# reverb.net
KiCad netlist of a schematic drawn in EAGLE
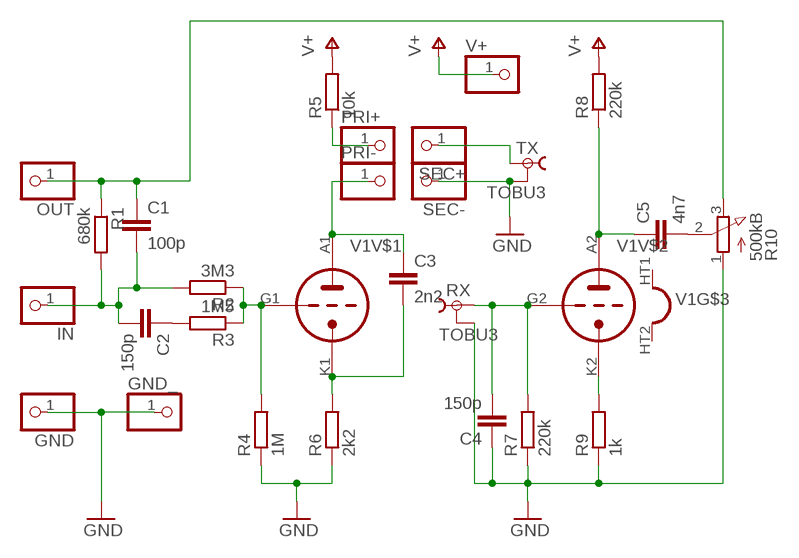
[diagram p0: schematic, sheet 1]

(export (version "E")
  (design (tool "Eeschema 10.0.6"))
  (components
    (comp (ref "C1")
      (value "100p")
      (footprint "eagle-import:C050-030X075")
      (libsource (lib "eagle-import") (part "C-EU050-030X075"))
    )
    (comp (ref "C2")
      (value "150p")
      (footprint "eagle-import:C050-030X075")
      (libsource (lib "eagle-import") (part "C-EU050-030X075"))
    )
    (comp (ref "C3")
      (value "2n2")
      (footprint "eagle-import:C050-030X075")
      (libsource (lib "eagle-import") (part "C-EU050-030X075"))
    )
    (comp (ref "C4")
      (value "150p")
      (footprint "eagle-import:C050-030X075")
      (libsource (lib "eagle-import") (part "C-EU050-030X075"))
    )
    (comp (ref "C5")
      (value "4n7")
      (footprint "eagle-import:C050-045X075")
      (libsource (lib "eagle-import") (part "C-EU050-045X075"))
    )
    (comp (ref "GND")
      (value "PINHD-1X1")
      (footprint "eagle-import:1X01")
      (libsource (lib "eagle-import") (part "PINHD-1X1"))
    )
    (comp (ref "GND_")
      (value "PINHD-1X1")
      (footprint "eagle-import:1X01")
      (libsource (lib "eagle-import") (part "PINHD-1X1"))
    )
    (comp (ref "IN")
      (value "PINHD-1X1")
      (footprint "eagle-import:1X01")
      (libsource (lib "eagle-import") (part "PINHD-1X1"))
    )
    (comp (ref "OUT")
      (value "PINHD-1X1")
      (footprint "eagle-import:1X01")
      (libsource (lib "eagle-import") (part "PINHD-1X1"))
    )
    (comp (ref "PRI+")
      (value "PINHD-1X1")
      (footprint "eagle-import:1X01")
      (libsource (lib "eagle-import") (part "PINHD-1X1"))
    )
    (comp (ref "PRI-")
      (value "PINHD-1X1")
      (footprint "eagle-import:1X01")
      (libsource (lib "eagle-import") (part "PINHD-1X1"))
    )
    (comp (ref "R1")
      (value "680k")
      (footprint "eagle-import:0207_7")
      (libsource (lib "eagle-import") (part "R-EU_0207/7"))
    )
    (comp (ref "R2")
      (value "3M3")
      (footprint "eagle-import:0207_7")
      (libsource (lib "eagle-import") (part "R-EU_0207/7"))
    )
    (comp (ref "R3")
      (value "1M5")
      (footprint "eagle-import:0207_7")
      (libsource (lib "eagle-import") (part "R-EU_0207/7"))
    )
    (comp (ref "R4")
      (value "1M")
      (footprint "eagle-import:0207_7")
      (libsource (lib "eagle-import") (part "R-EU_0207/7"))
    )
    (comp (ref "R5")
      (value "10k")
      (footprint "eagle-import:0207_7")
      (libsource (lib "eagle-import") (part "R-EU_0207/7"))
    )
    (comp (ref "R6")
      (value "2k2")
      (footprint "eagle-import:0207_7")
      (libsource (lib "eagle-import") (part "R-EU_0207/7"))
    )
    (comp (ref "R7")
      (value "220k")
      (footprint "eagle-import:0207_7")
      (libsource (lib "eagle-import") (part "R-EU_0207/7"))
    )
    (comp (ref "R8")
      (value "220k")
      (footprint "eagle-import:0207_7")
      (libsource (lib "eagle-import") (part "R-EU_0207/7"))
    )
    (comp (ref "R9")
      (value "1k")
      (footprint "eagle-import:0207_7")
      (libsource (lib "eagle-import") (part "R-EU_0207/7"))
    )
    (comp (ref "R10")
      (value "500kB")
      (footprint "eagle-import:3RP_1610N")
      (libsource (lib "eagle-import") (part "3RP/1610N"))
    )
    (comp (ref "RX")
      (value "TOBU3")
      (footprint "eagle-import:TOBU3")
      (fields (field (name "MF") "FARNELL") (field (name "MPN") "TOBU 3"))
      (libsource (lib "eagle-import") (part "TOBU3"))
    )
    (comp (ref "SEC+")
      (value "PINHD-1X1")
      (footprint "eagle-import:1X01")
      (libsource (lib "eagle-import") (part "PINHD-1X1"))
    )
    (comp (ref "SEC-")
      (value "PINHD-1X1")
      (footprint "eagle-import:1X01")
      (libsource (lib "eagle-import") (part "PINHD-1X1"))
    )
    (comp (ref "TX")
      (value "TOBU3")
      (footprint "eagle-import:TOBU3")
      (fields (field (name "MF") "FARNELL") (field (name "MPN") "TOBU 3"))
      (libsource (lib "eagle-import") (part "TOBU3"))
    )
    (comp (ref "V+")
      (value "PINHD-1X1")
      (footprint "eagle-import:1X01")
      (libsource (lib "eagle-import") (part "PINHD-1X1"))
    )
    (comp (ref "V1")
      (value "6NXX-PIT")
      (footprint "eagle-import:6NXX-PIT")
      (libsource (lib "eagle-import") (part "6NXX-PIT"))
    )
  )
  (nets
    (net (code "1") (name "GND") (class "Default")
      (node (ref "C4") (pin "1") (pinfunction "1_1") (pintype "passive"))
      (node (ref "GND") (pin "1") (pinfunction "1_1") (pintype "passive"))
      (node (ref "GND_") (pin "1") (pinfunction "1_1") (pintype "passive"))
      (node (ref "R10") (pin "1") (pinfunction "A_1") (pintype "passive"))
      (node (ref "R4") (pin "1") (pinfunction "1_1") (pintype "passive"))
      (node (ref "R6") (pin "1") (pinfunction "1_1") (pintype "passive"))
      (node (ref "R7") (pin "1") (pinfunction "1_1") (pintype "passive"))
      (node (ref "R9") (pin "1") (pinfunction "1_1") (pintype "passive"))
      (node (ref "RX") (pin "2") (pinfunction "2_2") (pintype "passive"))
      (node (ref "RX") (pin "2@1") (pinfunction "2_2@1") (pintype "passive"))
      (node (ref "RX") (pin "2@2") (pinfunction "2_2@2") (pintype "passive"))
      (node (ref "SEC-") (pin "1") (pinfunction "1_1") (pintype "passive"))
      (node (ref "TX") (pin "2") (pinfunction "2_2") (pintype "passive"))
      (node (ref "TX") (pin "2@1") (pinfunction "2_2@1") (pintype "passive"))
      (node (ref "TX") (pin "2@2") (pinfunction "2_2@2") (pintype "passive"))
    )
    (net (code "2") (name "Net-(C1-Pad2)") (class "Default")
      (node (ref "C1") (pin "2") (pinfunction "2_2") (pintype "passive"))
      (node (ref "C2") (pin "2") (pinfunction "2_2") (pintype "passive"))
      (node (ref "IN") (pin "1") (pinfunction "1_1") (pintype "passive"))
      (node (ref "R1") (pin "2") (pinfunction "2_2") (pintype "passive"))
      (node (ref "R2") (pin "2") (pinfunction "2_2") (pintype "passive"))
    )
    (net (code "3") (name "Net-(C2-Pad1)") (class "Default")
      (node (ref "C2") (pin "1") (pinfunction "1_1") (pintype "passive"))
      (node (ref "R3") (pin "2") (pinfunction "2_2") (pintype "passive"))
    )
    (net (code "4") (name "Net-(PRI+-Pad1)") (class "Default")
      (node (ref "PRI+") (pin "1") (pinfunction "1_1") (pintype "passive"))
      (node (ref "R5") (pin "1") (pinfunction "1_1") (pintype "passive"))
    )
    (net (code "5") (name "Net-(R10-E)") (class "Default")
      (node (ref "C1") (pin "1") (pinfunction "1_1") (pintype "passive"))
      (node (ref "OUT") (pin "1") (pinfunction "1_1") (pintype "passive"))
      (node (ref "R1") (pin "1") (pinfunction "1_1") (pintype "passive"))
      (node (ref "R10") (pin "3") (pinfunction "E_3") (pintype "passive"))
    )
    (net (code "6") (name "Net-(R10-S)") (class "Default")
      (node (ref "C5") (pin "2") (pinfunction "2_2") (pintype "passive"))
      (node (ref "R10") (pin "2") (pinfunction "S_2") (pintype "passive"))
    )
    (net (code "7") (name "Net-(SEC+-Pad1)") (class "Default")
      (node (ref "SEC+") (pin "1") (pinfunction "1_1") (pintype "passive"))
      (node (ref "TX") (pin "1") (pinfunction "1_1") (pintype "passive"))
    )
    (net (code "8") (name "Net-(V1B-TA)") (class "Default")
      (node (ref "C3") (pin "1") (pinfunction "1_1") (pintype "passive"))
      (node (ref "PRI-") (pin "1") (pinfunction "1_1") (pintype "passive"))
      (node (ref "V1") (pin "A1") (pinfunction "TA_A1") (pintype "passive"))
    )
    (net (code "9") (name "Net-(V1B-TG)") (class "Default")
      (node (ref "R2") (pin "1") (pinfunction "1_1") (pintype "passive"))
      (node (ref "R3") (pin "1") (pinfunction "1_1") (pintype "passive"))
      (node (ref "R4") (pin "2") (pinfunction "2_2") (pintype "passive"))
      (node (ref "V1") (pin "G1") (pinfunction "TG_G1") (pintype "passive"))
    )
    (net (code "10") (name "Net-(V1B-TK)") (class "Default")
      (node (ref "C3") (pin "2") (pinfunction "2_2") (pintype "passive"))
      (node (ref "R6") (pin "2") (pinfunction "2_2") (pintype "passive"))
      (node (ref "V1") (pin "K1") (pinfunction "TK_K1") (pintype "passive"))
    )
    (net (code "11") (name "Net-(V1C-TA)") (class "Default")
      (node (ref "C5") (pin "1") (pinfunction "1_1") (pintype "passive"))
      (node (ref "R8") (pin "1") (pinfunction "1_1") (pintype "passive"))
      (node (ref "V1") (pin "A2") (pinfunction "TA_A2") (pintype "passive"))
    )
    (net (code "12") (name "Net-(V1C-TG)") (class "Default")
      (node (ref "C4") (pin "2") (pinfunction "2_2") (pintype "passive"))
      (node (ref "R7") (pin "2") (pinfunction "2_2") (pintype "passive"))
      (node (ref "RX") (pin "1") (pinfunction "1_1") (pintype "passive"))
      (node (ref "V1") (pin "G2") (pinfunction "TG_G2") (pintype "passive"))
    )
    (net (code "13") (name "Net-(V1C-TK)") (class "Default")
      (node (ref "R9") (pin "2") (pinfunction "2_2") (pintype "passive"))
      (node (ref "V1") (pin "K2") (pinfunction "TK_K2") (pintype "passive"))
    )
    (net (code "14") (name "V+") (class "Default")
      (node (ref "R5") (pin "2") (pinfunction "2_2") (pintype "passive"))
      (node (ref "R8") (pin "2") (pinfunction "2_2") (pintype "passive"))
      (node (ref "V+") (pin "1") (pinfunction "1_1") (pintype "passive"))
    )
    (net (code "15") (name "unconnected-(V1A-H1-PadHT1)") (class "Default")
      (node (ref "V1") (pin "HT1") (pinfunction "H1_HT1") (pintype "passive"))
    )
    (net (code "16") (name "unconnected-(V1A-H2-PadHT2)") (class "Default")
      (node (ref "V1") (pin "HT2") (pinfunction "H2_HT2") (pintype "passive"))
    )
  )
)
